# SCH_WatiBattery_2024-12-09.net
KiCad netlist of a schematic drawn in EasyEDA
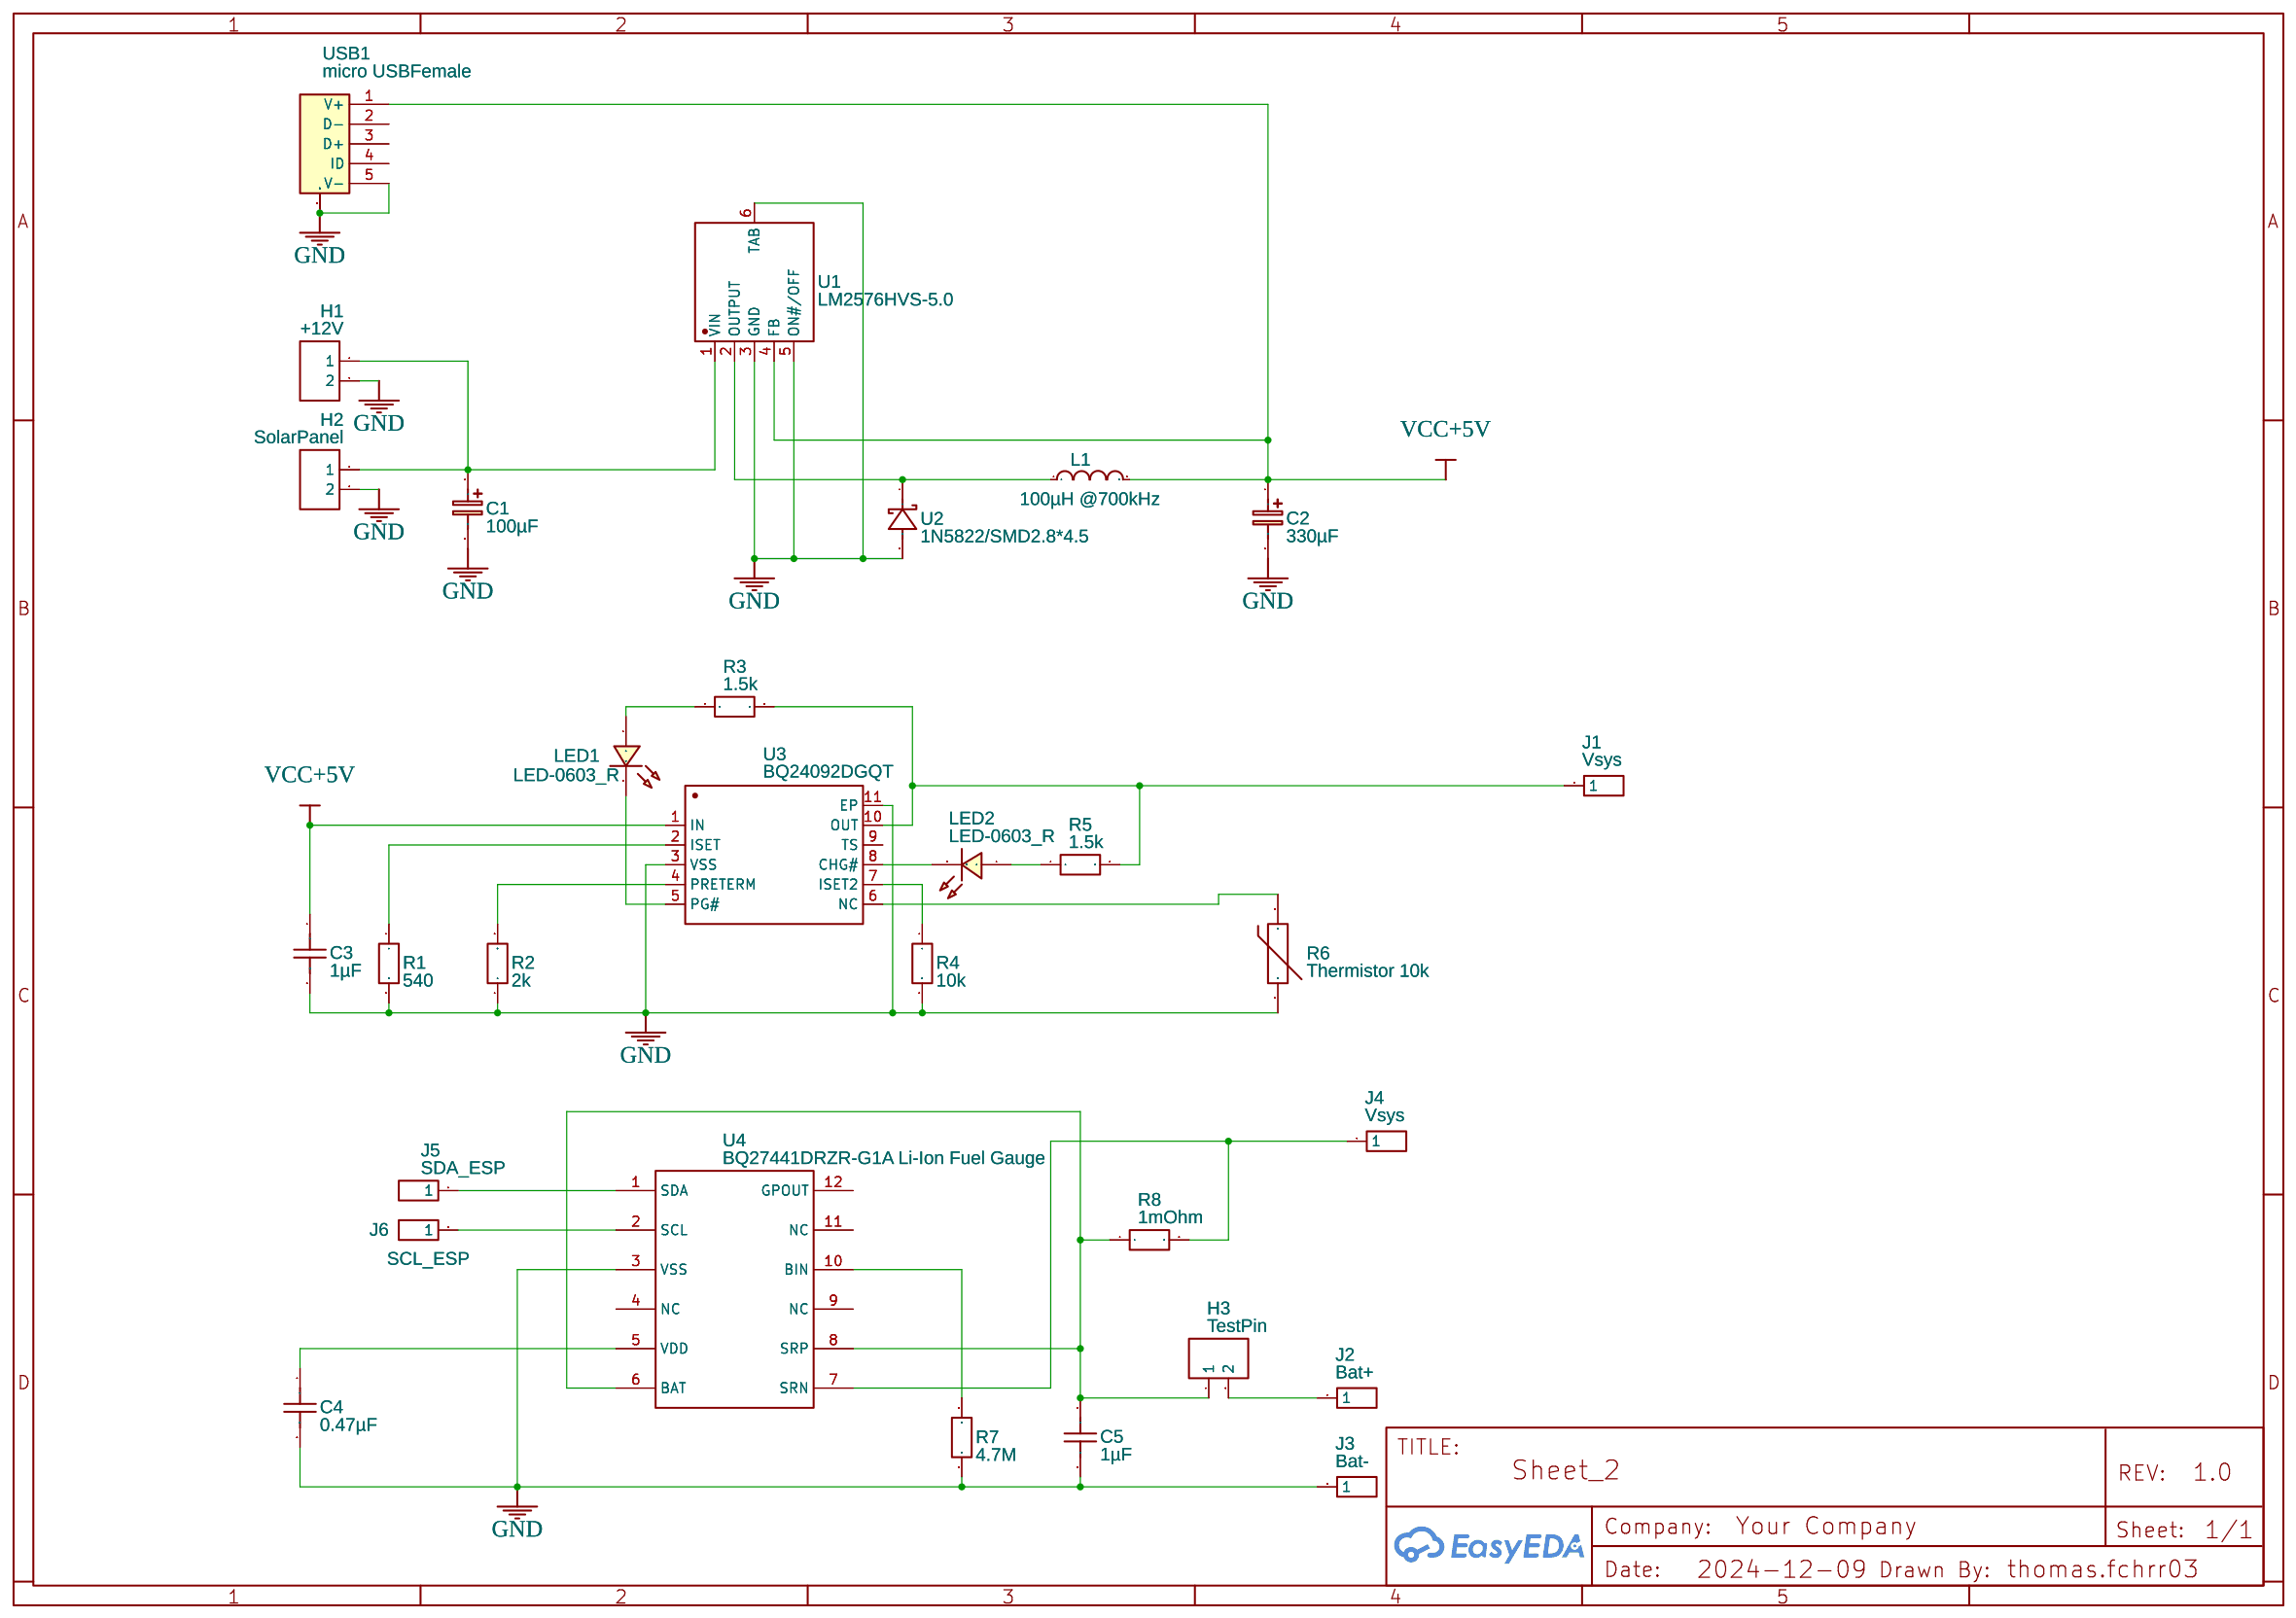
[diagram p0: schematic sheet]

(export (version "E")
  (design (tool "Eeschema 10.0.6"))
  (components
    (comp (ref "C1") (value "100µF") (libsource (lib "") (part "C_Tan_SMD_A_EU_1")))
    (comp (ref "C2") (value "330µF") (libsource (lib "") (part "C_Tan_SMD_A_EU")))
    (comp (ref "C3") (value "1µF") (libsource (lib "") (part "C_0603_US")))
    (comp (ref "C4") (value "0.47µF") (libsource (lib "") (part "C_0603_US")))
    (comp (ref "C5") (value "1µF") (libsource (lib "") (part "C_0603_US")))
    (comp (ref "H1") (value "+12V") (libsource (lib "") (part "HDR-F-2.54_1x2")))
    (comp (ref "H2") (value "SolarPanel") (libsource (lib "") (part "HDR-F-2.54_1x2")))
    (comp (ref "H3") (value "TestPin") (libsource (lib "") (part "HDR-F-2.54_1x2_1")))
    (comp (ref "J1") (value "Vsys") (libsource (lib "") (part "HDR-M-2.54_1x1_1")))
    (comp (ref "J2") (value "Bat+") (libsource (lib "") (part "HDR-M-2.54_1x1_1")))
    (comp (ref "J3") (value "Bat-") (libsource (lib "") (part "HDR-M-2.54_1x1_1")))
    (comp (ref "J4") (value "Vsys") (libsource (lib "") (part "HDR-M-2.54_1x1_1")))
    (comp (ref "J5") (value "SDA_ESP") (libsource (lib "") (part "HDR-M-2.54_1x1")))
    (comp (ref "J6") (value "SCL_ESP") (libsource (lib "") (part "HDR-M-2.54_1x1")))
    (comp (ref "L1") (value "100µH @700kHz") (libsource (lib "") (part "L0603_US")))
    (comp (ref "LED1")
      (value "LED-0603_R")
      (fields
        (field (name "Manufacturer Part") "19-217/R6C-AL1M2VY/3T")
        (field (name "Manufacturer") "EVERLIGHT(台湾亿光)")
      )
      (libsource (lib "") (part "LED-0603_R"))
    )
    (comp (ref "LED2")
      (value "LED-0603_R")
      (fields
        (field (name "Manufacturer Part") "19-217/R6C-AL1M2VY/3T")
        (field (name "Manufacturer") "EVERLIGHT(台湾亿光)")
      )
      (libsource (lib "") (part "LED-0603_R_1"))
    )
    (comp (ref "R1") (value "540") (libsource (lib "") (part "R_0603_EU")))
    (comp (ref "R2") (value "2k") (libsource (lib "") (part "R_0603_EU_1")))
    (comp (ref "R3") (value "1.5k") (libsource (lib "") (part "R_0603_EU_2")))
    (comp (ref "R4") (value "10k") (libsource (lib "") (part "R_0603_EU")))
    (comp (ref "R5") (value "1.5k") (libsource (lib "") (part "R_0603_EU_2")))
    (comp (ref "R6")
      (value "Thermistor 10k")
      (fields (field (name "Manufacturer Part") "MF52A1502F3470") (field (name "Manufacturer") "Shiheng"))
      (libsource (lib "") (part "Thermistance"))
    )
    (comp (ref "R7") (value "4.7M") (libsource (lib "") (part "R_0603_EU")))
    (comp (ref "R8") (value "1mOhm") (libsource (lib "") (part "R_0603_EU_2")))
    (comp (ref "U1")
      (value "LM2576HVS-5.0")
      (fields (field (name "Manufacturer") "UMW(友台半导体)"))
      (libsource (lib "") (part "LM2576HVS-5.0"))
    )
    (comp (ref "U2") (value "1N5822/SMD2.8*4.5") (libsource (lib "") (part "1N5822/SMD2.8*4.5")))
    (comp (ref "U3")
      (value "BQ24092DGQT")
      (fields (field (name "Manufacturer") "TI(德州仪器)"))
      (libsource (lib "") (part "BQ24092DGQT"))
    )
    (comp (ref "U4")
      (value "BQ27441DRZR-G1A Li-Ion Fuel Gauge")
      (libsource (lib "") (part "BQ27441DRZR-G1A Li-Ion Fuel Gauge"))
    )
    (comp (ref "USB1")
      (value "micro USBFemale")
      (fields (field (name "Manufacturer Part") "920-E52A2021S10100") (field (name "Manufacturer") "精拓金"))
      (libsource (lib "") (part "micro USBFemale"))
    )
  )
  (nets
    (net (code "1") (name "GND") (class "Default")
      (node (ref "C1") (pin "2") (pinfunction "2_2") (pintype "unspecified"))
      (node (ref "C2") (pin "2") (pinfunction "2_2") (pintype "unspecified"))
      (node (ref "C3") (pin "2") (pinfunction "2_2") (pintype "unspecified"))
      (node (ref "C4") (pin "2") (pinfunction "2_2") (pintype "unspecified"))
      (node (ref "C5") (pin "2") (pinfunction "2_2") (pintype "unspecified"))
      (node (ref "H1") (pin "2") (pinfunction "2_2") (pintype "input"))
      (node (ref "H2") (pin "2") (pinfunction "2_2") (pintype "input"))
      (node (ref "J3") (pin "1") (pinfunction "1_1") (pintype "input"))
      (node (ref "R1") (pin "2") (pinfunction "2_2") (pintype "unspecified"))
      (node (ref "R2") (pin "1") (pinfunction "1_1") (pintype "unspecified"))
      (node (ref "R4") (pin "2") (pinfunction "2_2") (pintype "unspecified"))
      (node (ref "R6") (pin "2") (pinfunction "2_2") (pintype "unspecified"))
      (node (ref "R7") (pin "2") (pinfunction "2_2") (pintype "unspecified"))
      (node (ref "U1") (pin "3") (pinfunction "GND_3") (pintype "unspecified"))
      (node (ref "U1") (pin "5") (pinfunction "ON#/OFF_5") (pintype "unspecified"))
      (node (ref "U1") (pin "6") (pinfunction "TAB_6") (pintype "unspecified"))
      (node (ref "U2") (pin "2") (pinfunction "K_2") (pintype "unspecified"))
      (node (ref "U3") (pin "11") (pinfunction "EP_11") (pintype "unspecified"))
      (node (ref "U3") (pin "3") (pinfunction "VSS_3") (pintype "unspecified"))
      (node (ref "U4") (pin "3") (pinfunction "VSS_3") (pintype "unspecified"))
      (node (ref "USB1") (pin "5") (pinfunction "V-_5") (pintype "unspecified"))
      (node (ref "USB1") (pin "SH0") (pinfunction "MTN_SH0") (pintype "input"))
      (node (ref "USB1") (pin "SH1") (pinfunction "1_SH1") (pintype "unspecified"))
      (node (ref "USB1") (pin "SH2") (pinfunction "2_SH2") (pintype "unspecified"))
      (node (ref "USB1") (pin "SH3") (pinfunction "3_SH3") (pintype "unspecified"))
    )
    (net (code "2") (name "Net-(H3-Pad2)") (class "Default")
      (node (ref "H3") (pin "2") (pinfunction "2_2") (pintype "input"))
      (node (ref "J2") (pin "1") (pinfunction "1_1") (pintype "input"))
    )
    (net (code "3") (name "Net-(LED1-Pad1)") (class "Default")
      (node (ref "LED1") (pin "1") (pinfunction "1_1") (pintype "unspecified"))
      (node (ref "R3") (pin "1") (pinfunction "1_1") (pintype "unspecified"))
    )
    (net (code "4") (name "Net-(LED2-Pad1)") (class "Default")
      (node (ref "LED2") (pin "1") (pinfunction "1_1") (pintype "unspecified"))
      (node (ref "R5") (pin "1") (pinfunction "1_1") (pintype "unspecified"))
    )
    (net (code "5") (name "Net-(U1-OUTPUT)") (class "Default")
      (node (ref "L1") (pin "1") (pinfunction "1_1") (pintype "unspecified"))
      (node (ref "U1") (pin "2") (pinfunction "OUTPUT_2") (pintype "unspecified"))
      (node (ref "U2") (pin "1") (pinfunction "A_1") (pintype "unspecified"))
    )
    (net (code "6") (name "Net-(U1-VIN)") (class "Default")
      (node (ref "C1") (pin "1") (pinfunction "1_1") (pintype "unspecified"))
      (node (ref "H1") (pin "1") (pinfunction "1_1") (pintype "input"))
      (node (ref "H2") (pin "1") (pinfunction "1_1") (pintype "input"))
      (node (ref "U1") (pin "1") (pinfunction "VIN_1") (pintype "unspecified"))
    )
    (net (code "7") (name "Net-(U3-CHG#)") (class "Default")
      (node (ref "LED2") (pin "2") (pinfunction "2_2") (pintype "unspecified"))
      (node (ref "U3") (pin "8") (pinfunction "CHG#_8") (pintype "unspecified"))
    )
    (net (code "8") (name "Net-(U3-ISET)") (class "Default")
      (node (ref "R1") (pin "1") (pinfunction "1_1") (pintype "unspecified"))
      (node (ref "U3") (pin "2") (pinfunction "ISET_2") (pintype "unspecified"))
    )
    (net (code "9") (name "Net-(U3-ISET2)") (class "Default")
      (node (ref "R4") (pin "1") (pinfunction "1_1") (pintype "unspecified"))
      (node (ref "U3") (pin "7") (pinfunction "ISET2_7") (pintype "unspecified"))
    )
    (net (code "10") (name "Net-(U3-NC)") (class "Default")
      (node (ref "R6") (pin "1") (pinfunction "1_1") (pintype "unspecified"))
      (node (ref "U3") (pin "6") (pinfunction "NC_6") (pintype "unspecified"))
    )
    (net (code "11") (name "Net-(U3-OUT)") (class "Default")
      (node (ref "J1") (pin "1") (pinfunction "1_1") (pintype "input"))
      (node (ref "R3") (pin "2") (pinfunction "2_2") (pintype "unspecified"))
      (node (ref "R5") (pin "2") (pinfunction "2_2") (pintype "unspecified"))
      (node (ref "U3") (pin "10") (pinfunction "OUT_10") (pintype "unspecified"))
    )
    (net (code "12") (name "Net-(U3-PG#)") (class "Default")
      (node (ref "LED1") (pin "2") (pinfunction "2_2") (pintype "unspecified"))
      (node (ref "U3") (pin "5") (pinfunction "PG#_5") (pintype "unspecified"))
    )
    (net (code "13") (name "Net-(U3-PRETERM)") (class "Default")
      (node (ref "R2") (pin "2") (pinfunction "2_2") (pintype "unspecified"))
      (node (ref "U3") (pin "4") (pinfunction "PRETERM_4") (pintype "unspecified"))
    )
    (net (code "14") (name "Net-(U4-BAT)") (class "Default")
      (node (ref "C5") (pin "1") (pinfunction "1_1") (pintype "unspecified"))
      (node (ref "H3") (pin "1") (pinfunction "1_1") (pintype "input"))
      (node (ref "R8") (pin "1") (pinfunction "1_1") (pintype "unspecified"))
      (node (ref "U4") (pin "6") (pinfunction "BAT_6") (pintype "unspecified"))
      (node (ref "U4") (pin "8") (pinfunction "SRP_8") (pintype "unspecified"))
    )
    (net (code "15") (name "Net-(U4-BIN)") (class "Default")
      (node (ref "R7") (pin "1") (pinfunction "1_1") (pintype "unspecified"))
      (node (ref "U4") (pin "10") (pinfunction "BIN_10") (pintype "unspecified"))
    )
    (net (code "16") (name "Net-(U4-SCL)") (class "Default")
      (node (ref "J6") (pin "1") (pinfunction "1_1") (pintype "input"))
      (node (ref "U4") (pin "2") (pinfunction "SCL_2") (pintype "unspecified"))
    )
    (net (code "17") (name "Net-(U4-SDA)") (class "Default")
      (node (ref "J5") (pin "1") (pinfunction "1_1") (pintype "input"))
      (node (ref "U4") (pin "1") (pinfunction "SDA_1") (pintype "unspecified"))
    )
    (net (code "18") (name "Net-(U4-SRN)") (class "Default")
      (node (ref "J4") (pin "1") (pinfunction "1_1") (pintype "input"))
      (node (ref "R8") (pin "2") (pinfunction "2_2") (pintype "unspecified"))
      (node (ref "U4") (pin "7") (pinfunction "SRN_7") (pintype "unspecified"))
    )
    (net (code "19") (name "Net-(U4-VDD)") (class "Default")
      (node (ref "C4") (pin "1") (pinfunction "1_1") (pintype "unspecified"))
      (node (ref "U4") (pin "5") (pinfunction "VDD_5") (pintype "unspecified"))
    )
    (net (code "20") (name "VCC+5V") (class "Default")
      (node (ref "C2") (pin "1") (pinfunction "1_1") (pintype "unspecified"))
      (node (ref "C3") (pin "1") (pinfunction "1_1") (pintype "unspecified"))
      (node (ref "L1") (pin "2") (pinfunction "2_2") (pintype "unspecified"))
      (node (ref "U1") (pin "4") (pinfunction "FB_4") (pintype "unspecified"))
      (node (ref "U3") (pin "1") (pinfunction "IN_1") (pintype "unspecified"))
      (node (ref "USB1") (pin "1") (pinfunction "V+_1") (pintype "unspecified"))
    )
    (net (code "21") (name "unconnected-(U3-TS-Pad9)") (class "Default")
      (node (ref "U3") (pin "9") (pinfunction "TS_9") (pintype "unspecified"))
    )
    (net (code "22") (name "unconnected-(U4-GPOUT-Pad12)") (class "Default")
      (node (ref "U4") (pin "12") (pinfunction "GPOUT_12") (pintype "unspecified"))
    )
    (net (code "23") (name "unconnected-(U4-NC-Pad4)") (class "Default")
      (node (ref "U4") (pin "4") (pinfunction "NC_4") (pintype "unspecified"))
    )
    (net (code "24") (name "unconnected-(U4-NC-Pad9)") (class "Default")
      (node (ref "U4") (pin "9") (pinfunction "NC_9") (pintype "unspecified"))
    )
    (net (code "25") (name "unconnected-(U4-NC-Pad11)") (class "Default")
      (node (ref "U4") (pin "11") (pinfunction "NC_11") (pintype "unspecified"))
    )
    (net (code "26") (name "unconnected-(USB1-D+-Pad3)") (class "Default")
      (node (ref "USB1") (pin "3") (pinfunction "D+_3") (pintype "unspecified"))
    )
    (net (code "27") (name "unconnected-(USB1-D--Pad2)") (class "Default")
      (node (ref "USB1") (pin "2") (pinfunction "D-_2") (pintype "unspecified"))
    )
    (net (code "28") (name "unconnected-(USB1-ID-Pad4)") (class "Default")
      (node (ref "USB1") (pin "4") (pinfunction "ID_4") (pintype "unspecified"))
    )
  )
)
